# ramanSpectrometer_contolBoard.net
KiCad netlist of a schematic drawn in EAGLE
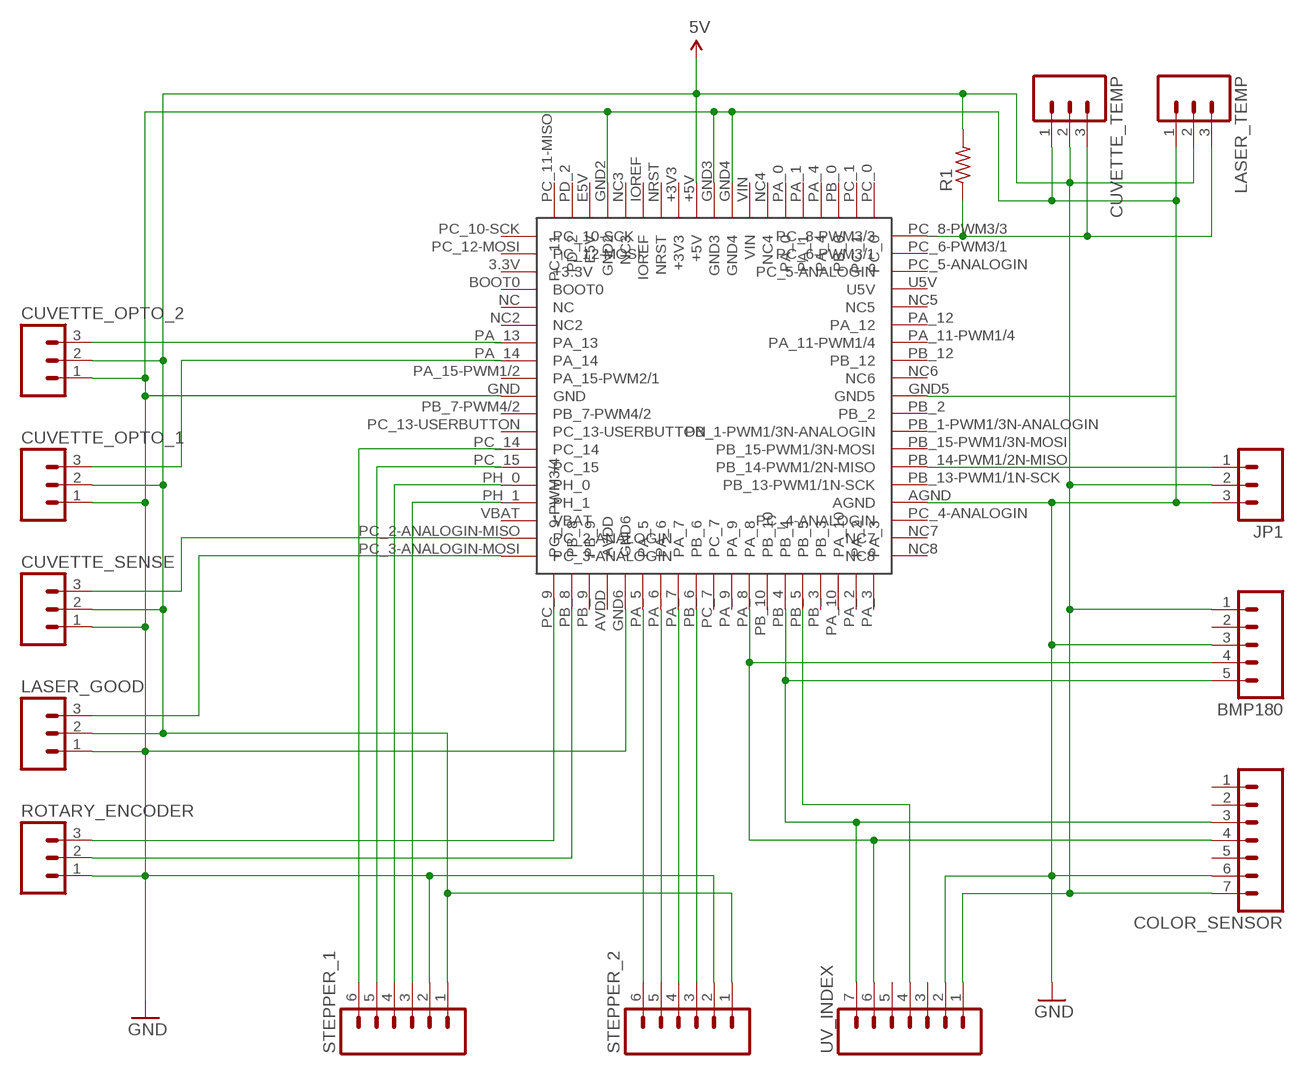
[diagram p0: schematic, sheet 1]

(export (version "E")
  (design (tool "Eeschema 10.0.6"))
  (components
    (comp (ref "BMP180")
      (value "M05PTH")
      (footprint "eagle-import:1X05")
      (libsource (lib "eagle-import") (part "M05PTH"))
    )
    (comp (ref "COLOR_SENSOR")
      (value "M07")
      (footprint "eagle-import:1X07")
      (libsource (lib "eagle-import") (part "M07"))
    )
    (comp (ref "CUVETTE_OPTO_1")
      (value "M03JST-PTH-VERT")
      (footprint "eagle-import:JST-3-PTH-VERT")
      (libsource (lib "eagle-import") (part "M03JST-PTH-VERT"))
    )
    (comp (ref "CUVETTE_OPTO_2")
      (value "M03JST-PTH-VERT")
      (footprint "eagle-import:JST-3-PTH-VERT")
      (libsource (lib "eagle-import") (part "M03JST-PTH-VERT"))
    )
    (comp (ref "CUVETTE_SENSE")
      (value "M03JST-PTH-VERT")
      (footprint "eagle-import:JST-3-PTH-VERT")
      (libsource (lib "eagle-import") (part "M03JST-PTH-VERT"))
    )
    (comp (ref "CUVETTE_TEMP")
      (value "M03JST-PTH-VERT")
      (footprint "eagle-import:JST-3-PTH-VERT")
      (libsource (lib "eagle-import") (part "M03JST-PTH-VERT"))
    )
    (comp (ref "JP1")
      (value "M03PTH")
      (footprint "eagle-import:1X03")
      (libsource (lib "eagle-import") (part "M03PTH"))
    )
    (comp (ref "LASER_GOOD")
      (value "M03JST-PTH-VERT")
      (footprint "eagle-import:JST-3-PTH-VERT")
      (libsource (lib "eagle-import") (part "M03JST-PTH-VERT"))
    )
    (comp (ref "LASER_TEMP")
      (value "M03JST-PTH-VERT")
      (footprint "eagle-import:JST-3-PTH-VERT")
      (libsource (lib "eagle-import") (part "M03JST-PTH-VERT"))
    )
    (comp (ref "R1")
      (value "R-US_M1206")
      (footprint "eagle-import:M1206")
      (libsource (lib "eagle-import") (part "R-US_M1206"))
    )
    (comp (ref "ROTARY_ENCODER")
      (value "M03JST-PTH-VERT")
      (footprint "eagle-import:JST-3-PTH-VERT")
      (libsource (lib "eagle-import") (part "M03JST-PTH-VERT"))
    )
    (comp (ref "STEPPER_1")
      (value "M06SIP")
      (footprint "eagle-import:1X06")
      (libsource (lib "eagle-import") (part "M06SIP"))
    )
    (comp (ref "STEPPER_2")
      (value "M06SIP")
      (footprint "eagle-import:1X06")
      (libsource (lib "eagle-import") (part "M06SIP"))
    )
    (comp (ref "U$1")
      (value "STNUCLEOF401RE")
      (footprint "eagle-import:F401-RE")
      (libsource (lib "eagle-import") (part "STNUCLEOF401RE"))
    )
    (comp (ref "UV_INDEX")
      (value "M07")
      (footprint "eagle-import:1X07")
      (libsource (lib "eagle-import") (part "M07"))
    )
  )
  (nets
    (net (code "1") (name "/+3.3V") (class "Default")
      (node (ref "U$1") (pin "3.3V") (pinfunction "+3.3V_3.3V") (pintype "power_in"))
    )
    (net (code "2") (name "/AVDD") (class "Default")
      (node (ref "U$1") (pin "AVDD") (pinfunction "AVDD_AVDD") (pintype "power_in"))
    )
    (net (code "3") (name "/E5V") (class "Default")
      (node (ref "U$1") (pin "E5V") (pinfunction "E5V_E5V") (pintype "power_in"))
    )
    (net (code "4") (name "/NC6") (class "Default")
      (node (ref "U$1") (pin "NC6") (pinfunction "NC6_NC6") (pintype "power_in"))
    )
    (net (code "5") (name "/VBAT") (class "Default")
      (node (ref "U$1") (pin "VBAT") (pinfunction "VBAT_VBAT") (pintype "power_in"))
    )
    (net (code "6") (name "5V") (class "Default")
      (node (ref "BMP180") (pin "1") (pinfunction "1_1") (pintype "passive"))
      (node (ref "COLOR_SENSOR") (pin "7") (pinfunction "7_7") (pintype "passive"))
      (node (ref "CUVETTE_OPTO_1") (pin "2") (pinfunction "2_2") (pintype "passive"))
      (node (ref "CUVETTE_OPTO_2") (pin "2") (pinfunction "2_2") (pintype "passive"))
      (node (ref "CUVETTE_SENSE") (pin "2") (pinfunction "2_2") (pintype "passive"))
      (node (ref "CUVETTE_TEMP") (pin "2") (pinfunction "2_2") (pintype "passive"))
      (node (ref "JP1") (pin "2") (pinfunction "2_2") (pintype "passive"))
      (node (ref "LASER_GOOD") (pin "2") (pinfunction "2_2") (pintype "passive"))
      (node (ref "LASER_TEMP") (pin "2") (pinfunction "2_2") (pintype "passive"))
      (node (ref "R1") (pin "2") (pinfunction "2_2") (pintype "passive"))
      (node (ref "STEPPER_1") (pin "1") (pinfunction "1_1") (pintype "passive"))
      (node (ref "STEPPER_2") (pin "1") (pinfunction "1_1") (pintype "passive"))
      (node (ref "U$1") (pin "+5V") (pinfunction "+5V_+5V") (pintype "bidirectional"))
      (node (ref "UV_INDEX") (pin "1") (pinfunction "1_1") (pintype "passive"))
    )
    (net (code "7") (name "GND") (class "Default")
      (node (ref "BMP180") (pin "3") (pinfunction "3_3") (pintype "passive"))
      (node (ref "COLOR_SENSOR") (pin "6") (pinfunction "6_6") (pintype "passive"))
      (node (ref "CUVETTE_OPTO_1") (pin "1") (pinfunction "1_1") (pintype "passive"))
      (node (ref "CUVETTE_OPTO_2") (pin "1") (pinfunction "1_1") (pintype "passive"))
      (node (ref "CUVETTE_SENSE") (pin "1") (pinfunction "1_1") (pintype "passive"))
      (node (ref "CUVETTE_TEMP") (pin "1") (pinfunction "1_1") (pintype "passive"))
      (node (ref "JP1") (pin "3") (pinfunction "3_3") (pintype "passive"))
      (node (ref "LASER_GOOD") (pin "1") (pinfunction "1_1") (pintype "passive"))
      (node (ref "LASER_TEMP") (pin "1") (pinfunction "1_1") (pintype "passive"))
      (node (ref "ROTARY_ENCODER") (pin "1") (pinfunction "1_1") (pintype "passive"))
      (node (ref "STEPPER_1") (pin "2") (pinfunction "2_2") (pintype "passive"))
      (node (ref "STEPPER_2") (pin "2") (pinfunction "2_2") (pintype "passive"))
      (node (ref "U$1") (pin "AGND") (pinfunction "AGND_AGND") (pintype "power_in"))
      (node (ref "U$1") (pin "GND") (pinfunction "GND_GND") (pintype "power_in"))
      (node (ref "U$1") (pin "GND2") (pinfunction "GND2_GND2") (pintype "power_in"))
      (node (ref "U$1") (pin "GND3") (pinfunction "GND3_GND3") (pintype "bidirectional"))
      (node (ref "U$1") (pin "GND4") (pinfunction "GND4_GND4") (pintype "bidirectional"))
      (node (ref "U$1") (pin "GND5") (pinfunction "GND5_GND5") (pintype "bidirectional"))
      (node (ref "U$1") (pin "GND6") (pinfunction "GND6_GND6") (pintype "bidirectional"))
      (node (ref "UV_INDEX") (pin "2") (pinfunction "2_2") (pintype "passive"))
    )
    (net (code "8") (name "Net-(BMP180-Pad4)") (class "Default")
      (node (ref "BMP180") (pin "4") (pinfunction "4_4") (pintype "passive"))
      (node (ref "COLOR_SENSOR") (pin "4") (pinfunction "4_4") (pintype "passive"))
      (node (ref "U$1") (pin "PA_8") (pinfunction "PA_8_PA_8") (pintype "bidirectional"))
      (node (ref "UV_INDEX") (pin "6") (pinfunction "6_6") (pintype "passive"))
    )
    (net (code "9") (name "Net-(BMP180-Pad5)") (class "Default")
      (node (ref "BMP180") (pin "5") (pinfunction "5_5") (pintype "passive"))
      (node (ref "COLOR_SENSOR") (pin "3") (pinfunction "3_3") (pintype "passive"))
      (node (ref "U$1") (pin "PB_4") (pinfunction "PB_4_PB_4") (pintype "bidirectional"))
      (node (ref "UV_INDEX") (pin "7") (pinfunction "7_7") (pintype "passive"))
    )
    (net (code "10") (name "Net-(CUVETTE_OPTO_1-Pad3)") (class "Default")
      (node (ref "CUVETTE_OPTO_1") (pin "3") (pinfunction "3_3") (pintype "passive"))
      (node (ref "U$1") (pin "PA_14") (pinfunction "PA_14_PA_14") (pintype "bidirectional"))
    )
    (net (code "11") (name "Net-(CUVETTE_OPTO_2-Pad3)") (class "Default")
      (node (ref "CUVETTE_OPTO_2") (pin "3") (pinfunction "3_3") (pintype "passive"))
      (node (ref "U$1") (pin "PA_13") (pinfunction "PA_13_PA_13") (pintype "bidirectional"))
    )
    (net (code "12") (name "Net-(CUVETTE_TEMP-Pad3)") (class "Default")
      (node (ref "CUVETTE_TEMP") (pin "3") (pinfunction "3_3") (pintype "passive"))
      (node (ref "LASER_TEMP") (pin "3") (pinfunction "3_3") (pintype "passive"))
      (node (ref "R1") (pin "1") (pinfunction "1_1") (pintype "passive"))
      (node (ref "U$1") (pin "PC_8-PWM3/3") (pinfunction "PC_8-PWM3/3_PC_8-PWM3/3") (pintype "bidirectional"))
    )
    (net (code "13") (name "Net-(JP1-Pad1)") (class "Default")
      (node (ref "JP1") (pin "1") (pinfunction "1_1") (pintype "passive"))
      (node (ref "U$1") (pin "PB_14-PWM1/2N-MISO") (pinfunction "PB_14-PWM1/2N-MISO_PB_14-PWM1/2N-MISO") (pintype "bidirectional"))
    )
    (net (code "14") (name "Net-(ROTARY_ENCODER-Pad2)") (class "Default")
      (node (ref "ROTARY_ENCODER") (pin "2") (pinfunction "2_2") (pintype "passive"))
      (node (ref "U$1") (pin "PB_8") (pinfunction "PB_8_PB_8") (pintype "bidirectional"))
    )
    (net (code "15") (name "Net-(STEPPER_1-Pad3)") (class "Default")
      (node (ref "STEPPER_1") (pin "3") (pinfunction "3_3") (pintype "passive"))
      (node (ref "U$1") (pin "PH_1") (pinfunction "PH_1_PH_1") (pintype "bidirectional"))
    )
    (net (code "16") (name "Net-(STEPPER_1-Pad4)") (class "Default")
      (node (ref "STEPPER_1") (pin "4") (pinfunction "4_4") (pintype "passive"))
      (node (ref "U$1") (pin "PH_0") (pinfunction "PH_0_PH_0") (pintype "bidirectional"))
    )
    (net (code "17") (name "Net-(STEPPER_1-Pad5)") (class "Default")
      (node (ref "STEPPER_1") (pin "5") (pinfunction "5_5") (pintype "passive"))
      (node (ref "U$1") (pin "PC_15") (pinfunction "PC_15_PC_15") (pintype "bidirectional"))
    )
    (net (code "18") (name "Net-(STEPPER_1-Pad6)") (class "Default")
      (node (ref "STEPPER_1") (pin "6") (pinfunction "6_6") (pintype "passive"))
      (node (ref "U$1") (pin "PC_14") (pinfunction "PC_14_PC_14") (pintype "bidirectional"))
    )
    (net (code "19") (name "Net-(STEPPER_2-Pad3)") (class "Default")
      (node (ref "STEPPER_2") (pin "3") (pinfunction "3_3") (pintype "passive"))
      (node (ref "U$1") (pin "PB_6") (pinfunction "PB_6_PB_6") (pintype "bidirectional"))
    )
    (net (code "20") (name "Net-(STEPPER_2-Pad4)") (class "Default")
      (node (ref "STEPPER_2") (pin "4") (pinfunction "4_4") (pintype "passive"))
      (node (ref "U$1") (pin "PA_7") (pinfunction "PA_7_PA_7") (pintype "bidirectional"))
    )
    (net (code "21") (name "Net-(STEPPER_2-Pad5)") (class "Default")
      (node (ref "STEPPER_2") (pin "5") (pinfunction "5_5") (pintype "passive"))
      (node (ref "U$1") (pin "PA_6") (pinfunction "PA_6_PA_6") (pintype "bidirectional"))
    )
    (net (code "22") (name "Net-(STEPPER_2-Pad6)") (class "Default")
      (node (ref "STEPPER_2") (pin "6") (pinfunction "6_6") (pintype "passive"))
      (node (ref "U$1") (pin "PA_5") (pinfunction "PA_5_PA_5") (pintype "bidirectional"))
    )
    (net (code "23") (name "Net-(U$1-PC_2-ANALOGIN)") (class "Default")
      (node (ref "CUVETTE_SENSE") (pin "3") (pinfunction "3_3") (pintype "passive"))
      (node (ref "U$1") (pin "PC_2-ANALOGIN-MISO") (pinfunction "PC_2-ANALOGIN_PC_2-ANALOGIN-MISO") (pintype "bidirectional"))
    )
    (net (code "24") (name "Net-(U$1-PC_3-ANALOGIN)") (class "Default")
      (node (ref "LASER_GOOD") (pin "3") (pinfunction "3_3") (pintype "passive"))
      (node (ref "U$1") (pin "PC_3-ANALOGIN-MOSI") (pinfunction "PC_3-ANALOGIN_PC_3-ANALOGIN-MOSI") (pintype "bidirectional"))
    )
    (net (code "25") (name "Net-(U$1-PC_9-PWM3{slash}4)") (class "Default")
      (node (ref "ROTARY_ENCODER") (pin "3") (pinfunction "3_3") (pintype "passive"))
      (node (ref "U$1") (pin "PC_9") (pinfunction "PC_9-PWM3/4_PC_9") (pintype "bidirectional"))
    )
    (net (code "26") (name "Net-(U$1-PadPB_5)") (class "Default")
      (node (ref "U$1") (pin "PB_5") (pinfunction "PB_5_PB_5") (pintype "bidirectional"))
      (node (ref "UV_INDEX") (pin "4") (pinfunction "4_4") (pintype "passive"))
    )
    (net (code "27") (name "unconnected-(BMP180-Pad2)") (class "Default")
      (node (ref "BMP180") (pin "2") (pinfunction "2_2") (pintype "passive"))
    )
    (net (code "28") (name "unconnected-(COLOR_SENSOR-Pad1)") (class "Default")
      (node (ref "COLOR_SENSOR") (pin "1") (pinfunction "1_1") (pintype "passive"))
    )
    (net (code "29") (name "unconnected-(COLOR_SENSOR-Pad2)") (class "Default")
      (node (ref "COLOR_SENSOR") (pin "2") (pinfunction "2_2") (pintype "passive"))
    )
    (net (code "30") (name "unconnected-(COLOR_SENSOR-Pad5)") (class "Default")
      (node (ref "COLOR_SENSOR") (pin "5") (pinfunction "5_5") (pintype "passive"))
    )
    (net (code "31") (name "unconnected-(U$1-PA_15-PWM2{slash}1-PadPA_15-PWM1{slash}2)") (class "Default")
      (node (ref "U$1") (pin "PA_15-PWM1/2") (pinfunction "PA_15-PWM2/1_PA_15-PWM1/2") (pintype "bidirectional"))
    )
    (net (code "32") (name "unconnected-(U$1-PC_11-PadPC_11-MISO)") (class "Default")
      (node (ref "U$1") (pin "PC_11-MISO") (pinfunction "PC_11_PC_11-MISO") (pintype "bidirectional"))
    )
    (net (code "33") (name "unconnected-(U$1-Pad+3V3)") (class "Default")
      (node (ref "U$1") (pin "+3V3") (pinfunction "+3V3_+3V3") (pintype "bidirectional"))
    )
    (net (code "34") (name "unconnected-(U$1-PadBOOT0)") (class "Default")
      (node (ref "U$1") (pin "BOOT0") (pinfunction "BOOT0_BOOT0") (pintype "bidirectional"))
    )
    (net (code "35") (name "unconnected-(U$1-PadIOREF)") (class "Default")
      (node (ref "U$1") (pin "IOREF") (pinfunction "IOREF_IOREF") (pintype "bidirectional"))
    )
    (net (code "36") (name "unconnected-(U$1-PadNC)") (class "Default")
      (node (ref "U$1") (pin "NC") (pinfunction "NC_NC") (pintype "no_connect"))
    )
    (net (code "37") (name "unconnected-(U$1-PadNC2)") (class "Default")
      (node (ref "U$1") (pin "NC2") (pinfunction "NC2_NC2") (pintype "no_connect"))
    )
    (net (code "38") (name "unconnected-(U$1-PadNC3)") (class "Default")
      (node (ref "U$1") (pin "NC3") (pinfunction "NC3_NC3") (pintype "no_connect"))
    )
    (net (code "39") (name "unconnected-(U$1-PadNC4)") (class "Default")
      (node (ref "U$1") (pin "NC4") (pinfunction "NC4_NC4") (pintype "bidirectional"))
    )
    (net (code "40") (name "unconnected-(U$1-PadNC5)") (class "Default")
      (node (ref "U$1") (pin "NC5") (pinfunction "NC5_NC5") (pintype "bidirectional"))
    )
    (net (code "41") (name "unconnected-(U$1-PadNC7)") (class "Default")
      (node (ref "U$1") (pin "NC7") (pinfunction "NC7_NC7") (pintype "bidirectional"))
    )
    (net (code "42") (name "unconnected-(U$1-PadNC8)") (class "Default")
      (node (ref "U$1") (pin "NC8") (pinfunction "NC8_NC8") (pintype "bidirectional"))
    )
    (net (code "43") (name "unconnected-(U$1-PadNRST)") (class "Default")
      (node (ref "U$1") (pin "NRST") (pinfunction "NRST_NRST") (pintype "bidirectional"))
    )
    (net (code "44") (name "unconnected-(U$1-PadPA_0)") (class "Default")
      (node (ref "U$1") (pin "PA_0") (pinfunction "PA_0_PA_0") (pintype "bidirectional"))
    )
    (net (code "45") (name "unconnected-(U$1-PadPA_1)") (class "Default")
      (node (ref "U$1") (pin "PA_1") (pinfunction "PA_1_PA_1") (pintype "bidirectional"))
    )
    (net (code "46") (name "unconnected-(U$1-PadPA_2)") (class "Default")
      (node (ref "U$1") (pin "PA_2") (pinfunction "PA_2_PA_2") (pintype "bidirectional"))
    )
    (net (code "47") (name "unconnected-(U$1-PadPA_3)") (class "Default")
      (node (ref "U$1") (pin "PA_3") (pinfunction "PA_3_PA_3") (pintype "bidirectional"))
    )
    (net (code "48") (name "unconnected-(U$1-PadPA_4)") (class "Default")
      (node (ref "U$1") (pin "PA_4") (pinfunction "PA_4_PA_4") (pintype "bidirectional"))
    )
    (net (code "49") (name "unconnected-(U$1-PadPA_9)") (class "Default")
      (node (ref "U$1") (pin "PA_9") (pinfunction "PA_9_PA_9") (pintype "bidirectional"))
    )
    (net (code "50") (name "unconnected-(U$1-PadPA_10)") (class "Default")
      (node (ref "U$1") (pin "PA_10") (pinfunction "PA_10_PA_10") (pintype "bidirectional"))
    )
    (net (code "51") (name "unconnected-(U$1-PadPA_11-PWM1{slash}4)") (class "Default")
      (node (ref "U$1") (pin "PA_11-PWM1/4") (pinfunction "PA_11-PWM1/4_PA_11-PWM1/4") (pintype "bidirectional"))
    )
    (net (code "52") (name "unconnected-(U$1-PadPA_12)") (class "Default")
      (node (ref "U$1") (pin "PA_12") (pinfunction "PA_12_PA_12") (pintype "bidirectional"))
    )
    (net (code "53") (name "unconnected-(U$1-PadPB_0)") (class "Default")
      (node (ref "U$1") (pin "PB_0") (pinfunction "PB_0_PB_0") (pintype "bidirectional"))
    )
    (net (code "54") (name "unconnected-(U$1-PadPB_1-PWM1{slash}3N-ANALOGIN)") (class "Default")
      (node (ref "U$1") (pin "PB_1-PWM1/3N-ANALOGIN") (pinfunction "PB_1-PWM1/3N-ANALOGIN_PB_1-PWM1/3N-ANALOGIN") (pintype "bidirectional"))
    )
    (net (code "55") (name "unconnected-(U$1-PadPB_2)") (class "Default")
      (node (ref "U$1") (pin "PB_2") (pinfunction "PB_2_PB_2") (pintype "bidirectional"))
    )
    (net (code "56") (name "unconnected-(U$1-PadPB_3)") (class "Default")
      (node (ref "U$1") (pin "PB_3") (pinfunction "PB_3_PB_3") (pintype "bidirectional"))
    )
    (net (code "57") (name "unconnected-(U$1-PadPB_7-PWM4{slash}2)") (class "Default")
      (node (ref "U$1") (pin "PB_7-PWM4/2") (pinfunction "PB_7-PWM4/2_PB_7-PWM4/2") (pintype "bidirectional"))
    )
    (net (code "58") (name "unconnected-(U$1-PadPB_9)") (class "Default")
      (node (ref "U$1") (pin "PB_9") (pinfunction "PB_9_PB_9") (pintype "bidirectional"))
    )
    (net (code "59") (name "unconnected-(U$1-PadPB_10)") (class "Default")
      (node (ref "U$1") (pin "PB_10") (pinfunction "PB_10_PB_10") (pintype "bidirectional"))
    )
    (net (code "60") (name "unconnected-(U$1-PadPB_12)") (class "Default")
      (node (ref "U$1") (pin "PB_12") (pinfunction "PB_12_PB_12") (pintype "bidirectional"))
    )
    (net (code "61") (name "unconnected-(U$1-PadPB_13-PWM1{slash}1N-SCK)") (class "Default")
      (node (ref "U$1") (pin "PB_13-PWM1/1N-SCK") (pinfunction "PB_13-PWM1/1N-SCK_PB_13-PWM1/1N-SCK") (pintype "bidirectional"))
    )
    (net (code "62") (name "unconnected-(U$1-PadPB_15-PWM1{slash}3N-MOSI)") (class "Default")
      (node (ref "U$1") (pin "PB_15-PWM1/3N-MOSI") (pinfunction "PB_15-PWM1/3N-MOSI_PB_15-PWM1/3N-MOSI") (pintype "bidirectional"))
    )
    (net (code "63") (name "unconnected-(U$1-PadPC_0)") (class "Default")
      (node (ref "U$1") (pin "PC_0") (pinfunction "PC_0_PC_0") (pintype "bidirectional"))
    )
    (net (code "64") (name "unconnected-(U$1-PadPC_1)") (class "Default")
      (node (ref "U$1") (pin "PC_1") (pinfunction "PC_1_PC_1") (pintype "bidirectional"))
    )
    (net (code "65") (name "unconnected-(U$1-PadPC_4-ANALOGIN)") (class "Default")
      (node (ref "U$1") (pin "PC_4-ANALOGIN") (pinfunction "PC_4-ANALOGIN_PC_4-ANALOGIN") (pintype "bidirectional"))
    )
    (net (code "66") (name "unconnected-(U$1-PadPC_5-ANALOGIN)") (class "Default")
      (node (ref "U$1") (pin "PC_5-ANALOGIN") (pinfunction "PC_5-ANALOGIN_PC_5-ANALOGIN") (pintype "bidirectional"))
    )
    (net (code "67") (name "unconnected-(U$1-PadPC_6-PWM3{slash}1)") (class "Default")
      (node (ref "U$1") (pin "PC_6-PWM3/1") (pinfunction "PC_6-PWM3/1_PC_6-PWM3/1") (pintype "bidirectional"))
    )
    (net (code "68") (name "unconnected-(U$1-PadPC_7)") (class "Default")
      (node (ref "U$1") (pin "PC_7") (pinfunction "PC_7_PC_7") (pintype "bidirectional"))
    )
    (net (code "69") (name "unconnected-(U$1-PadPC_10-SCK)") (class "Default")
      (node (ref "U$1") (pin "PC_10-SCK") (pinfunction "PC_10-SCK_PC_10-SCK") (pintype "bidirectional"))
    )
    (net (code "70") (name "unconnected-(U$1-PadPC_12-MOSI)") (class "Default")
      (node (ref "U$1") (pin "PC_12-MOSI") (pinfunction "PC_12-MOSI_PC_12-MOSI") (pintype "bidirectional"))
    )
    (net (code "71") (name "unconnected-(U$1-PadPC_13-USERBUTTON)") (class "Default")
      (node (ref "U$1") (pin "PC_13-USERBUTTON") (pinfunction "PC_13-USERBUTTON_PC_13-USERBUTTON") (pintype "bidirectional"))
    )
    (net (code "72") (name "unconnected-(U$1-PadPD_2)") (class "Default")
      (node (ref "U$1") (pin "PD_2") (pinfunction "PD_2_PD_2") (pintype "bidirectional"))
    )
    (net (code "73") (name "unconnected-(U$1-PadU5V)") (class "Default")
      (node (ref "U$1") (pin "U5V") (pinfunction "U5V_U5V") (pintype "bidirectional"))
    )
    (net (code "74") (name "unconnected-(U$1-PadVIN)") (class "Default")
      (node (ref "U$1") (pin "VIN") (pinfunction "VIN_VIN") (pintype "bidirectional"))
    )
    (net (code "75") (name "unconnected-(UV_INDEX-Pad3)") (class "Default")
      (node (ref "UV_INDEX") (pin "3") (pinfunction "3_3") (pintype "passive"))
    )
    (net (code "76") (name "unconnected-(UV_INDEX-Pad5)") (class "Default")
      (node (ref "UV_INDEX") (pin "5") (pinfunction "5_5") (pintype "passive"))
    )
  )
)
